# ETH_PHY.net
KiCad netlist of a schematic drawn in Altium Designer
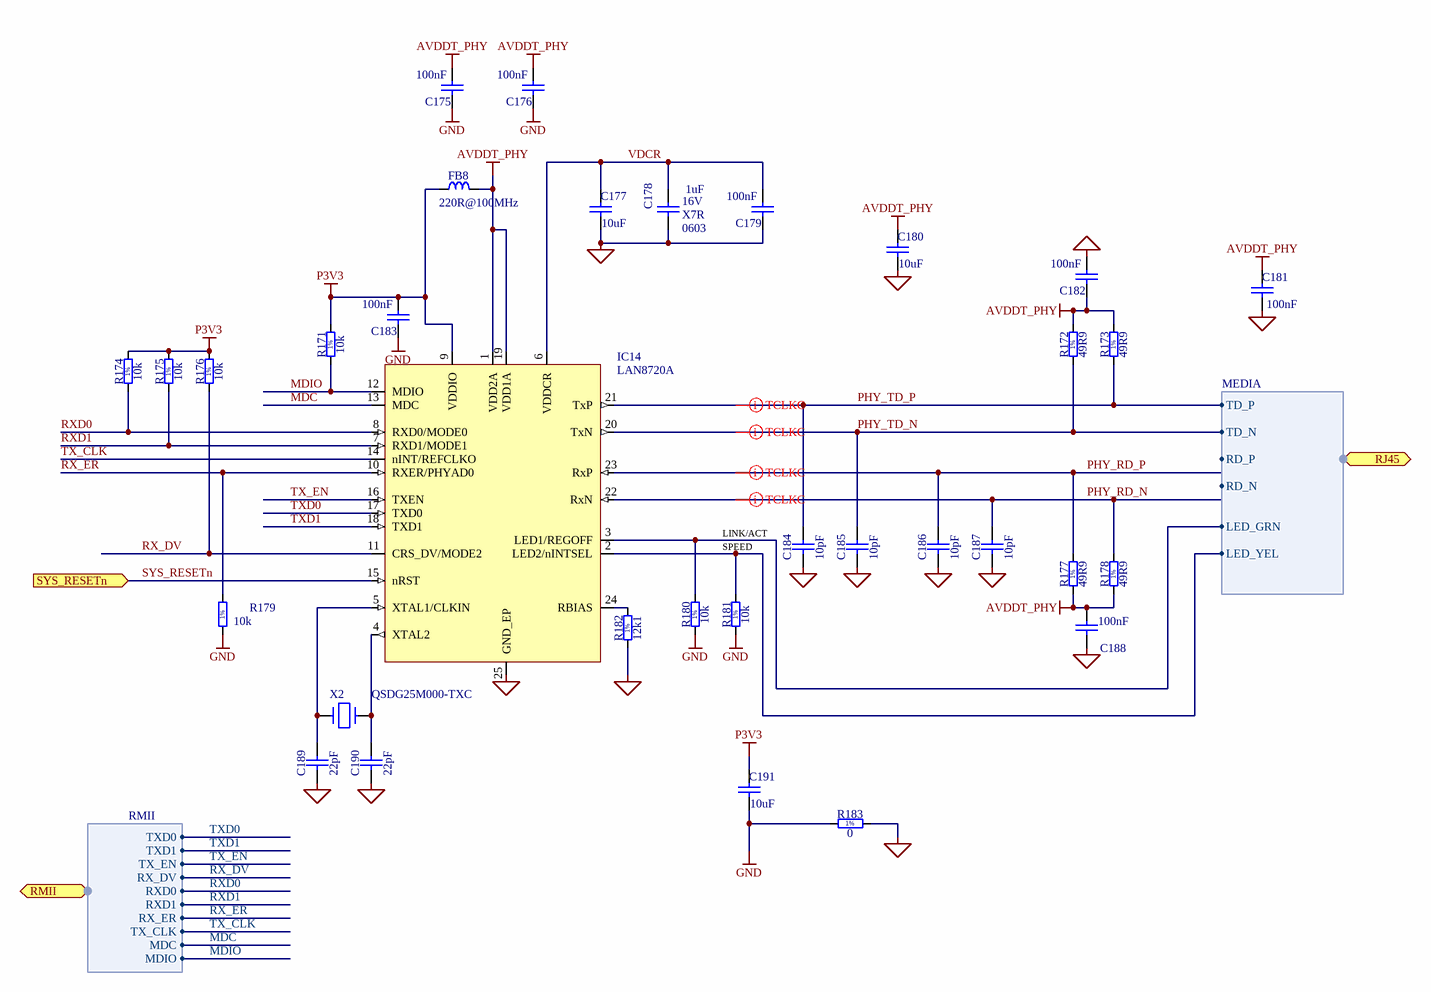
[diagram p0: ETH_PHY.SchDoc]

(export (version "E")
  (design (tool "Eeschema 10.0.6"))
  (components
    (comp (ref "C175")
      (value "100nF")
      (footprint "CAPC1005X55N")
      (description "Non-polarised capacitor")
      (fields
        (field (name "PART NUMBER") "CC0402_100NF_16V_10%_X7R")
        (field (name "VOLTAGE") "16V")
        (field (name "AUTHOR") "CERN DEM JLC")
      )
      (libsource (lib "Capacitors") (part "Capacitor - non polarized"))
    )
    (comp (ref "C176")
      (value "100nF")
      (footprint "CAPC1005X55N")
      (description "Non-polarised capacitor")
      (fields
        (field (name "PART NUMBER") "CC0402_100NF_16V_10%_X7R")
        (field (name "VOLTAGE") "16V")
        (field (name "AUTHOR") "CERN DEM JLC")
      )
      (libsource (lib "Capacitors") (part "Capacitor - non polarized"))
    )
    (comp (ref "C177")
      (value "10uF")
      (footprint "CAPC2012X135N")
      (description "Non-polarised capacitor")
      (fields
        (field (name "PART NUMBER") "CC0805_10UF_10V_10%_X7R")
        (field (name "VOLTAGE") "10V")
        (field (name "AUTHOR") "CERN DEM JLC")
      )
      (libsource (lib "Capacitors") (part "Capacitor - non polarized"))
    )
    (comp (ref "C178")
      (value "1uF")
      (footprint "CAPC1608X87N")
      (description "Non-polarised capacitor")
      (fields
        (field (name "PART NUMBER") "CC0603_1UF_16V_10%_X7R")
        (field (name "VOLTAGE") "16V")
        (field (name "TC") "X7R")
        (field (name "TOLERANCE") "±10%")
        (field (name "CASE") "0603")
        (field (name "AUTHOR") "CERN DEM JLC")
      )
      (libsource (lib "Capacitors") (part "Capacitor - non polarized"))
    )
    (comp (ref "C179")
      (value "100nF")
      (footprint "CAPC1005X55N")
      (description "Non-polarised capacitor")
      (fields
        (field (name "PART NUMBER") "CC0402_100NF_16V_10%_X7R")
        (field (name "VOLTAGE") "16V")
        (field (name "AUTHOR") "CERN DEM JLC")
      )
      (libsource (lib "Capacitors") (part "Capacitor - non polarized"))
    )
    (comp (ref "C180")
      (value "10uF")
      (footprint "CAPC2012X135N")
      (description "Non-polarised capacitor")
      (fields
        (field (name "PART NUMBER") "CC0805_10UF_10V_10%_X7R")
        (field (name "VOLTAGE") "10V")
        (field (name "AUTHOR") "CERN DEM JLC")
      )
      (libsource (lib "Capacitors") (part "Capacitor - non polarized"))
    )
    (comp (ref "C181")
      (value "100nF")
      (footprint "CAPC1005X55N")
      (description "Non-polarised capacitor")
      (fields
        (field (name "PART NUMBER") "CC0402_100NF_16V_10%_X7R")
        (field (name "VOLTAGE") "16V")
        (field (name "AUTHOR") "CERN DEM JLC")
      )
      (libsource (lib "Capacitors") (part "Capacitor - non polarized"))
    )
    (comp (ref "C182")
      (value "100nF")
      (footprint "CAPC1005X55N")
      (description "Non-polarised capacitor")
      (fields
        (field (name "PART NUMBER") "CC0402_100NF_16V_10%_X7R")
        (field (name "VOLTAGE") "16V")
        (field (name "AUTHOR") "CERN DEM JLC")
      )
      (libsource (lib "Capacitors") (part "Capacitor - non polarized"))
    )
    (comp (ref "C183")
      (value "100nF")
      (footprint "CAPC1005X55N")
      (description "Non-polarised capacitor")
      (fields
        (field (name "PART NUMBER") "CC0402_100NF_16V_10%_X7R")
        (field (name "VOLTAGE") "16V")
        (field (name "AUTHOR") "CERN DEM JLC")
      )
      (libsource (lib "Capacitors") (part "Capacitor - non polarized"))
    )
    (comp (ref "C184")
      (value "10pF")
      (footprint "CAPC1005X55N")
      (description "Non-polarised capacitor")
      (fields
        (field (name "PART NUMBER") "CC0402_10PF_50V_5%_NP0")
        (field (name "VOLTAGE") "50V")
        (field (name "AUTHOR") "CERN DEM JLC")
      )
      (libsource (lib "Capacitors") (part "Capacitor - non polarized"))
    )
    (comp (ref "C185")
      (value "10pF")
      (footprint "CAPC1005X55N")
      (description "Non-polarised capacitor")
      (fields
        (field (name "PART NUMBER") "CC0402_10PF_50V_5%_NP0")
        (field (name "VOLTAGE") "50V")
        (field (name "AUTHOR") "CERN DEM JLC")
      )
      (libsource (lib "Capacitors") (part "Capacitor - non polarized"))
    )
    (comp (ref "C186")
      (value "10pF")
      (footprint "CAPC1005X55N")
      (description "Non-polarised capacitor")
      (fields
        (field (name "PART NUMBER") "CC0402_10PF_50V_5%_NP0")
        (field (name "VOLTAGE") "50V")
        (field (name "AUTHOR") "CERN DEM JLC")
      )
      (libsource (lib "Capacitors") (part "Capacitor - non polarized"))
    )
    (comp (ref "C187")
      (value "10pF")
      (footprint "CAPC1005X55N")
      (description "Non-polarised capacitor")
      (fields
        (field (name "PART NUMBER") "CC0402_10PF_50V_5%_NP0")
        (field (name "VOLTAGE") "50V")
        (field (name "AUTHOR") "CERN DEM JLC")
      )
      (libsource (lib "Capacitors") (part "Capacitor - non polarized"))
    )
    (comp (ref "C188")
      (value "100nF")
      (footprint "CAPC1005X55N")
      (description "Non-polarised capacitor")
      (fields
        (field (name "PART NUMBER") "CC0402_100NF_16V_10%_X7R")
        (field (name "VOLTAGE") "16V")
        (field (name "AUTHOR") "CERN DEM JLC")
      )
      (libsource (lib "Capacitors") (part "Capacitor - non polarized"))
    )
    (comp (ref "C189")
      (value "22pF")
      (footprint "CAPC1005X55N")
      (description "Non-polarised capacitor")
      (fields
        (field (name "PART NUMBER") "CC0402_22PF_50V_5%_NP0")
        (field (name "VOLTAGE") "50V")
        (field (name "AUTHOR") "CERN DEM JLC")
      )
      (libsource (lib "Capacitors") (part "Capacitor - non polarized"))
    )
    (comp (ref "C190")
      (value "22pF")
      (footprint "CAPC1005X55N")
      (description "Non-polarised capacitor")
      (fields
        (field (name "PART NUMBER") "CC0402_22PF_50V_5%_NP0")
        (field (name "VOLTAGE") "50V")
        (field (name "AUTHOR") "CERN DEM JLC")
      )
      (libsource (lib "Capacitors") (part "Capacitor - non polarized"))
    )
    (comp (ref "C191")
      (value "10uF")
      (footprint "CAPC2012X135N")
      (description "Non-polarised capacitor")
      (fields
        (field (name "PART NUMBER") "CC0805_10UF_10V_10%_X7R")
        (field (name "VOLTAGE") "10V")
        (field (name "AUTHOR") "CERN DEM JLC")
      )
      (libsource (lib "Capacitors") (part "Capacitor - non polarized"))
    )
    (comp (ref "FB8")
      (value "220R@100MHz")
      (footprint "INDC2012X105N")
      (description "Inductor")
      (fields
        (field (name "PART NUMBER") "IND0805_MURATA_BLM21PG221SN1D")
        (field (name "POWER") "2A")
        (field (name "AUTHOR") "CERN DEM JLC")
      )
      (libsource (lib "Inductors & Transformers") (part "Inductor"))
    )
    (comp (ref "IC14")
      (value "LAN8720A")
      (footprint "QFN24-TP")
      (description "RMII ethernet transceiver with auto MIDIX")
      (libsource (lib "LIBRARY_SCH") (part "IFC_LAN8710A"))
    )
    (comp (ref "R171")
      (value "10k")
      (footprint "RESC1005X40N")
      (description "Resistor - 1%")
      (fields
        (field (name "PART NUMBER") "R0402_10K_1%_0.0625W_100PPM")
        (field (name "POWER") "0.0625W")
        (field (name "AUTHOR") "CERN DEM JLC")
      )
      (libsource (lib "Resistors") (part "Resistor - 1%"))
    )
    (comp (ref "R172")
      (value "49R9")
      (footprint "RESC1005X40N")
      (description "Resistor - 1%")
      (fields
        (field (name "PART NUMBER") "R0402_49R9_1%_0.0625W_100PPM")
        (field (name "POWER") "0.0625W")
        (field (name "AUTHOR") "CERN DEM JLC")
      )
      (libsource (lib "Resistors") (part "Resistor - 1%"))
    )
    (comp (ref "R173")
      (value "49R9")
      (footprint "RESC1005X40N")
      (description "Resistor - 1%")
      (fields
        (field (name "PART NUMBER") "R0402_49R9_1%_0.0625W_100PPM")
        (field (name "POWER") "0.0625W")
        (field (name "AUTHOR") "CERN DEM JLC")
      )
      (libsource (lib "Resistors") (part "Resistor - 1%"))
    )
    (comp (ref "R174")
      (value "10k")
      (footprint "RESC1005X40N")
      (description "Resistor - 1%")
      (fields
        (field (name "PART NUMBER") "R0402_10K_1%_0.0625W_100PPM")
        (field (name "POWER") "0.0625W")
        (field (name "AUTHOR") "CERN DEM JLC")
      )
      (libsource (lib "Resistors") (part "Resistor - 1%"))
    )
    (comp (ref "R175")
      (value "10k")
      (footprint "RESC1005X40N")
      (description "Resistor - 1%")
      (fields
        (field (name "PART NUMBER") "R0402_10K_1%_0.0625W_100PPM")
        (field (name "POWER") "0.0625W")
        (field (name "AUTHOR") "CERN DEM JLC")
      )
      (libsource (lib "Resistors") (part "Resistor - 1%"))
    )
    (comp (ref "R176")
      (value "10k")
      (footprint "RESC1005X40N")
      (description "Resistor - 1%")
      (fields
        (field (name "PART NUMBER") "R0402_10K_1%_0.0625W_100PPM")
        (field (name "POWER") "0.0625W")
        (field (name "AUTHOR") "CERN DEM JLC")
      )
      (libsource (lib "Resistors") (part "Resistor - 1%"))
    )
    (comp (ref "R177")
      (value "49R9")
      (footprint "RESC1005X40N")
      (description "Resistor - 1%")
      (fields
        (field (name "PART NUMBER") "R0402_49R9_1%_0.0625W_100PPM")
        (field (name "POWER") "0.0625W")
        (field (name "AUTHOR") "CERN DEM JLC")
      )
      (libsource (lib "Resistors") (part "Resistor - 1%"))
    )
    (comp (ref "R178")
      (value "49R9")
      (footprint "RESC1005X40N")
      (description "Resistor - 1%")
      (fields
        (field (name "PART NUMBER") "R0402_49R9_1%_0.0625W_100PPM")
        (field (name "POWER") "0.0625W")
        (field (name "AUTHOR") "CERN DEM JLC")
      )
      (libsource (lib "Resistors") (part "Resistor - 1%"))
    )
    (comp (ref "R179")
      (value "10k")
      (footprint "RESC1005X40N")
      (description "Resistor - 1%")
      (fields
        (field (name "PART NUMBER") "R0402_10K_1%_0.0625W_100PPM")
        (field (name "POWER") "0.0625W")
        (field (name "AUTHOR") "CERN DEM JLC")
      )
      (libsource (lib "Resistors") (part "Resistor - 1%"))
    )
    (comp (ref "R180")
      (value "10k")
      (footprint "RESC1005X40N")
      (description "Resistor - 1%")
      (fields
        (field (name "PART NUMBER") "R0402_10K_1%_0.0625W_100PPM")
        (field (name "POWER") "0.0625W")
        (field (name "AUTHOR") "CERN DEM JLC")
      )
      (libsource (lib "Resistors") (part "Resistor - 1%"))
    )
    (comp (ref "R181")
      (value "10k")
      (footprint "RESC1005X40N")
      (description "Resistor - 1%")
      (fields
        (field (name "PART NUMBER") "R0402_10K_1%_0.0625W_100PPM")
        (field (name "POWER") "0.0625W")
        (field (name "AUTHOR") "CERN DEM JLC")
      )
      (libsource (lib "Resistors") (part "Resistor - 1%"))
    )
    (comp (ref "R182")
      (value "12k1")
      (footprint "RESC1005X40N")
      (description "Resistor - 1%")
      (fields
        (field (name "PART NUMBER") "R0402_12K1_1%_0.0625W_100PPM")
        (field (name "POWER") "0.0625W")
        (field (name "AUTHOR") "CERN DEM JLC")
      )
      (libsource (lib "Resistors") (part "Resistor - 1%"))
    )
    (comp (ref "R183")
      (value "0")
      (footprint "RESC1608X55N")
      (description "Resistor - 1%")
      (fields
        (field (name "PART NUMBER") "R0603_0R_JUMPER")
        (field (name "MANUFACTURER") "GENERIC")
        (field (name "AUTHOR") "CERN DEM JLC")
      )
      (libsource (lib "Resistors") (part "Resistor - 1%"))
    )
    (comp (ref "X2")
      (value "QSDG25M000-TXC")
      (footprint "XTAL_5.0*3.2")
      (description "miniature crystal oscillator (Maritex)")
      (libsource (lib "LIBRARY_SCH") (part "X_CRYSTAL_SMD_5.0*3.2"))
    )
  )
  (nets
    (net (code "3") (name "/MDC") (class "Default")
      (node (ref "IC14") (pin "13") (pinfunction "MDC_13") (pintype "bidirectional"))
    )
    (net (code "4") (name "/MDIO") (class "Default")
      (node (ref "IC14") (pin "12") (pinfunction "MDIO_12") (pintype "bidirectional"))
      (node (ref "R171") (pin "1") (pinfunction "1_1") (pintype "passive"))
    )
    (net (code "5") (name "/PHY_RD_N") (class "Default")
      (node (ref "C187") (pin "2") (pinfunction "2_2") (pintype "passive"))
      (node (ref "IC14") (pin "22") (pinfunction "RxN_22") (pintype "input"))
      (node (ref "R178") (pin "2") (pinfunction "2_2") (pintype "passive"))
    )
    (net (code "6") (name "/PHY_RD_P") (class "Default")
      (node (ref "C186") (pin "2") (pinfunction "2_2") (pintype "passive"))
      (node (ref "IC14") (pin "23") (pinfunction "RxP_23") (pintype "input"))
      (node (ref "R177") (pin "2") (pinfunction "2_2") (pintype "passive"))
    )
    (net (code "7") (name "/PHY_TD_N") (class "Default")
      (node (ref "C185") (pin "2") (pinfunction "2_2") (pintype "passive"))
      (node (ref "IC14") (pin "20") (pinfunction "TxN_20") (pintype "output"))
      (node (ref "R172") (pin "1") (pinfunction "1_1") (pintype "passive"))
    )
    (net (code "8") (name "/PHY_TD_P") (class "Default")
      (node (ref "C184") (pin "2") (pinfunction "2_2") (pintype "passive"))
      (node (ref "IC14") (pin "21") (pinfunction "TxP_21") (pintype "output"))
      (node (ref "R173") (pin "1") (pinfunction "1_1") (pintype "passive"))
    )
    (net (code "9") (name "/RXD0") (class "Default")
      (node (ref "IC14") (pin "8") (pinfunction "RXD0/MODE0_8") (pintype "input"))
      (node (ref "R174") (pin "1") (pinfunction "1_1") (pintype "passive"))
    )
    (net (code "10") (name "/RXD1") (class "Default")
      (node (ref "IC14") (pin "7") (pinfunction "RXD1/MODE1_7") (pintype "input"))
      (node (ref "R175") (pin "1") (pinfunction "1_1") (pintype "passive"))
    )
    (net (code "11") (name "/RX_DV") (class "Default")
      (node (ref "IC14") (pin "11") (pinfunction "CRS_DV/MODE2_11") (pintype "bidirectional"))
      (node (ref "R176") (pin "1") (pinfunction "1_1") (pintype "passive"))
    )
    (net (code "12") (name "/RX_ER") (class "Default")
      (node (ref "IC14") (pin "10") (pinfunction "RXER/PHYAD0_10") (pintype "input"))
      (node (ref "R179") (pin "2") (pinfunction "2_2") (pintype "passive"))
    )
    (net (code "13") (name "/SYS_RESETn") (class "Default")
      (node (ref "IC14") (pin "15") (pinfunction "nRST_15") (pintype "input"))
    )
    (net (code "14") (name "/TXD0") (class "Default")
      (node (ref "IC14") (pin "17") (pinfunction "TXD0_17") (pintype "input"))
    )
    (net (code "15") (name "/TXD1") (class "Default")
      (node (ref "IC14") (pin "18") (pinfunction "TXD1_18") (pintype "input"))
    )
    (net (code "16") (name "/TX_CLK") (class "Default")
      (node (ref "IC14") (pin "14") (pinfunction "nINT/REFCLKO_14") (pintype "bidirectional"))
    )
    (net (code "17") (name "/TX_EN") (class "Default")
      (node (ref "IC14") (pin "16") (pinfunction "TXEN_16") (pintype "input"))
    )
    (net (code "18") (name "/VDCR") (class "Default")
      (node (ref "C177") (pin "1") (pinfunction "1_1") (pintype "passive"))
      (node (ref "C178") (pin "2") (pinfunction "2_2") (pintype "passive"))
      (node (ref "C179") (pin "1") (pinfunction "1_1") (pintype "passive"))
      (node (ref "IC14") (pin "6") (pinfunction "VDDCR_6") (pintype "power_in"))
    )
    (net (code "21") (name "AVDDT_PHY") (class "Default")
      (node (ref "C175") (pin "1") (pinfunction "1_1") (pintype "passive"))
      (node (ref "C176") (pin "1") (pinfunction "1_1") (pintype "passive"))
      (node (ref "C180") (pin "1") (pinfunction "1_1") (pintype "passive"))
      (node (ref "C181") (pin "2") (pinfunction "2_2") (pintype "passive"))
      (node (ref "C182") (pin "2") (pinfunction "2_2") (pintype "passive"))
      (node (ref "C188") (pin "1") (pinfunction "1_1") (pintype "passive"))
      (node (ref "FB8") (pin "2") (pinfunction "2_2") (pintype "passive"))
      (node (ref "IC14") (pin "1") (pinfunction "VDD2A_1") (pintype "power_in"))
      (node (ref "IC14") (pin "19") (pinfunction "VDD1A_19") (pintype "power_in"))
      (node (ref "R172") (pin "2") (pinfunction "2_2") (pintype "passive"))
      (node (ref "R173") (pin "2") (pinfunction "2_2") (pintype "passive"))
      (node (ref "R177") (pin "1") (pinfunction "1_1") (pintype "passive"))
      (node (ref "R178") (pin "1") (pinfunction "1_1") (pintype "passive"))
    )
    (net (code "22") (name "GND") (class "Default")
      (node (ref "C175") (pin "2") (pinfunction "2_2") (pintype "passive"))
      (node (ref "C176") (pin "2") (pinfunction "2_2") (pintype "passive"))
      (node (ref "C183") (pin "2") (pinfunction "2_2") (pintype "passive"))
      (node (ref "C191") (pin "2") (pinfunction "2_2") (pintype "passive"))
      (node (ref "R179") (pin "1") (pinfunction "1_1") (pintype "passive"))
      (node (ref "R180") (pin "1") (pinfunction "1_1") (pintype "passive"))
      (node (ref "R181") (pin "1") (pinfunction "1_1") (pintype "passive"))
      (node (ref "R183") (pin "1") (pinfunction "1_1") (pintype "passive"))
    )
    (net (code "23") (name "GND_ETH") (class "Default")
      (node (ref "C177") (pin "2") (pinfunction "2_2") (pintype "passive"))
      (node (ref "C178") (pin "1") (pinfunction "1_1") (pintype "passive"))
      (node (ref "C179") (pin "2") (pinfunction "2_2") (pintype "passive"))
      (node (ref "C180") (pin "2") (pinfunction "2_2") (pintype "passive"))
      (node (ref "C181") (pin "1") (pinfunction "1_1") (pintype "passive"))
      (node (ref "C182") (pin "1") (pinfunction "1_1") (pintype "passive"))
      (node (ref "C184") (pin "1") (pinfunction "1_1") (pintype "passive"))
      (node (ref "C185") (pin "1") (pinfunction "1_1") (pintype "passive"))
      (node (ref "C186") (pin "1") (pinfunction "1_1") (pintype "passive"))
      (node (ref "C187") (pin "1") (pinfunction "1_1") (pintype "passive"))
      (node (ref "C188") (pin "2") (pinfunction "2_2") (pintype "passive"))
      (node (ref "C189") (pin "1") (pinfunction "1_1") (pintype "passive"))
      (node (ref "C190") (pin "1") (pinfunction "1_1") (pintype "passive"))
      (node (ref "IC14") (pin "25") (pinfunction "GND_EP_25") (pintype "power_in"))
      (node (ref "R182") (pin "1") (pinfunction "1_1") (pintype "passive"))
      (node (ref "R183") (pin "2") (pinfunction "2_2") (pintype "passive"))
    )
    (net (code "24") (name "Net-(IC14-LED1{slash}REGOFF)") (class "Default")
      (node (ref "IC14") (pin "3") (pinfunction "LED1/REGOFF_3") (pintype "bidirectional"))
      (node (ref "R180") (pin "2") (pinfunction "2_2") (pintype "passive"))
    )
    (net (code "25") (name "Net-(IC14-LED2{slash}nINTSEL)") (class "Default")
      (node (ref "IC14") (pin "2") (pinfunction "LED2/nINTSEL_2") (pintype "bidirectional"))
      (node (ref "R181") (pin "2") (pinfunction "2_2") (pintype "passive"))
    )
    (net (code "26") (name "Net-(IC14-RBIAS)") (class "Default")
      (node (ref "IC14") (pin "24") (pinfunction "RBIAS_24") (pintype "passive"))
      (node (ref "R182") (pin "2") (pinfunction "2_2") (pintype "passive"))
    )
    (net (code "27") (name "Net-(IC14-XTAL1{slash}CLKIN)") (class "Default")
      (node (ref "C189") (pin "2") (pinfunction "2_2") (pintype "passive"))
      (node (ref "IC14") (pin "5") (pinfunction "XTAL1/CLKIN_5") (pintype "input"))
      (node (ref "X2") (pin "1") (pinfunction "1_1") (pintype "passive"))
    )
    (net (code "28") (name "Net-(IC14-XTAL2)") (class "Default")
      (node (ref "C190") (pin "2") (pinfunction "2_2") (pintype "passive"))
      (node (ref "IC14") (pin "4") (pinfunction "XTAL2_4") (pintype "output"))
      (node (ref "X2") (pin "2") (pinfunction "2_2") (pintype "passive"))
    )
    (net (code "29") (name "P3V3") (class "Default")
      (node (ref "C183") (pin "1") (pinfunction "1_1") (pintype "passive"))
      (node (ref "C191") (pin "1") (pinfunction "1_1") (pintype "passive"))
      (node (ref "FB8") (pin "1") (pinfunction "1_1") (pintype "passive"))
      (node (ref "IC14") (pin "9") (pinfunction "VDDIO_9") (pintype "power_in"))
      (node (ref "R171") (pin "2") (pinfunction "2_2") (pintype "passive"))
      (node (ref "R174") (pin "2") (pinfunction "2_2") (pintype "passive"))
      (node (ref "R175") (pin "2") (pinfunction "2_2") (pintype "passive"))
      (node (ref "R176") (pin "2") (pinfunction "2_2") (pintype "passive"))
    )
  )
)
